# Mainboard_JTAG_Connector.net
KiCad netlist of a schematic drawn in Altium Designer
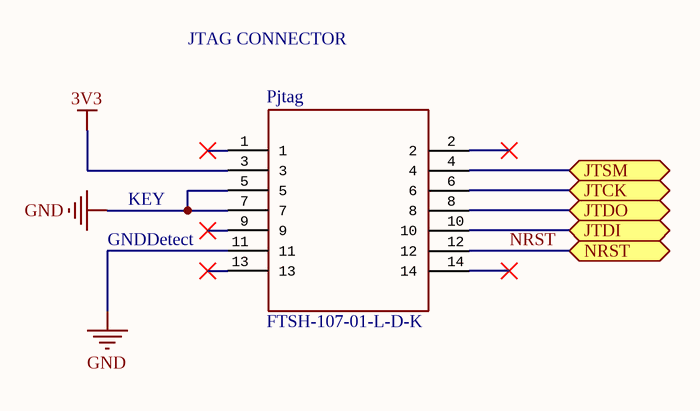
[diagram p0: Mainboard_JTAG Connector.SchDoc]

(export (version "E")
  (design (tool "Eeschema 10.0.6"))
  (components
    (comp (ref "Pjtag")
      (value "FTSH-107-01-L-D-K")
      (footprint "CN HDR JTAG")
      (description "Connector Header Through Hole 14 position 0.050\" (1.27mm)")
      (fields (field (name "MF") "Samtec Inc."))
      (libsource (lib "AltiumLibraries") (part "CN HDR JTAG"))
    )
  )
  (nets
    (net (code "1") (name "/JTCK") (class "Default")
      (node (ref "Pjtag") (pin "6") (pinfunction "6_6") (pintype "passive"))
    )
    (net (code "2") (name "/JTDI") (class "Default")
      (node (ref "Pjtag") (pin "10") (pinfunction "10_10") (pintype "passive"))
    )
    (net (code "3") (name "/JTDO") (class "Default")
      (node (ref "Pjtag") (pin "8") (pinfunction "8_8") (pintype "passive"))
    )
    (net (code "4") (name "/JTSM") (class "Default")
      (node (ref "Pjtag") (pin "4") (pinfunction "4_4") (pintype "passive"))
    )
    (net (code "5") (name "/NRST") (class "Default")
      (node (ref "Pjtag") (pin "12") (pinfunction "12_12") (pintype "passive"))
    )
    (net (code "6") (name "3V3") (class "Default")
      (node (ref "Pjtag") (pin "3") (pinfunction "3_3") (pintype "passive"))
    )
    (net (code "7") (name "GND") (class "Default")
      (node (ref "Pjtag") (pin "11") (pinfunction "11_11") (pintype "passive"))
      (node (ref "Pjtag") (pin "5") (pinfunction "5_5") (pintype "passive"))
      (node (ref "Pjtag") (pin "7") (pinfunction "7_7") (pintype "passive"))
    )
    (net (code "8") (name "unconnected-(Pjtag-Pad1)") (class "Default")
      (node (ref "Pjtag") (pin "1") (pinfunction "1_1") (pintype "passive+no_connect"))
    )
    (net (code "9") (name "unconnected-(Pjtag-Pad2)") (class "Default")
      (node (ref "Pjtag") (pin "2") (pinfunction "2_2") (pintype "passive+no_connect"))
    )
    (net (code "10") (name "unconnected-(Pjtag-Pad9)") (class "Default")
      (node (ref "Pjtag") (pin "9") (pinfunction "9_9") (pintype "passive+no_connect"))
    )
    (net (code "11") (name "unconnected-(Pjtag-Pad13)") (class "Default")
      (node (ref "Pjtag") (pin "13") (pinfunction "13_13") (pintype "passive+no_connect"))
    )
    (net (code "12") (name "unconnected-(Pjtag-Pad14)") (class "Default")
      (node (ref "Pjtag") (pin "14") (pinfunction "14_14") (pintype "passive+no_connect"))
    )
  )
)
